# Current_Transducer.net
KiCad netlist of a schematic drawn in Altium Designer
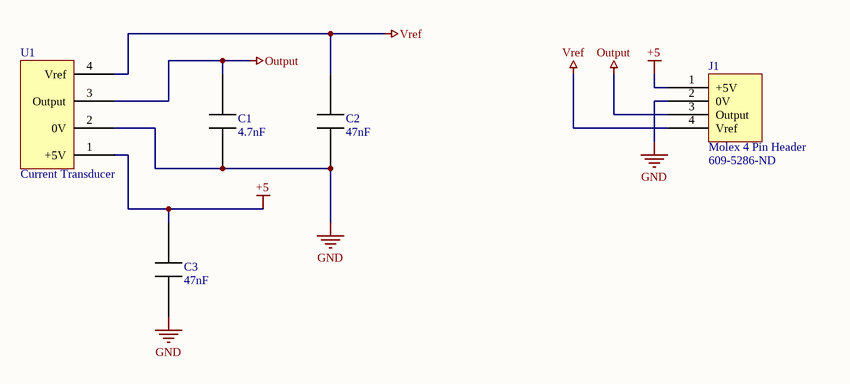
[diagram p0: Current Transducer.SchDoc]

(export (version "E")
  (design (tool "Eeschema 10.0.6"))
  (components
    (comp (ref "C1")
      (value "4.7nF")
      (footprint "CAPC2012X10N")
      (libsource (lib "Current Transducer") (part "47nF capacitor"))
    )
    (comp (ref "C2")
      (value "47nF")
      (footprint "CAPC2012X10N")
      (libsource (lib "Current Transducer") (part "47nF capacitor"))
    )
    (comp (ref "C3")
      (value "47nF")
      (footprint "CAPC2012X10N")
      (libsource (lib "Current Transducer") (part "47nF capacitor"))
    )
    (comp (ref "J1")
      (value "Molex 4 Pin Header")
      (footprint "4 Pin Header")
      (fields (field (name "SUPPLIER PART NUMBER 1") "609-5286-ND"))
      (libsource (lib "Current Transducer") (part "Molex 4 Pin Header"))
    )
    (comp (ref "U1")
      (value "Current Transducer")
      (footprint "Current Transducer")
      (libsource (lib "Current Transducer") (part "Current Transducer"))
    )
  )
  (nets
    (net (code "1") (name "+5") (class "Default")
      (node (ref "C3") (pin "2") (pinfunction "2_2") (pintype "passive"))
      (node (ref "J1") (pin "1") (pinfunction "+5V_1") (pintype "passive"))
      (node (ref "U1") (pin "1") (pinfunction "+5V_1") (pintype "passive"))
    )
    (net (code "2") (name "GND") (class "Default")
      (node (ref "C1") (pin "1") (pinfunction "1_1") (pintype "passive"))
      (node (ref "C2") (pin "1") (pinfunction "1_1") (pintype "passive"))
      (node (ref "C3") (pin "1") (pinfunction "1_1") (pintype "passive"))
      (node (ref "J1") (pin "2") (pinfunction "0V_2") (pintype "passive"))
      (node (ref "U1") (pin "2") (pinfunction "0V_2") (pintype "passive"))
    )
    (net (code "3") (name "Output") (class "Default")
      (node (ref "C1") (pin "2") (pinfunction "2_2") (pintype "passive"))
      (node (ref "J1") (pin "3") (pinfunction "Output_3") (pintype "passive"))
      (node (ref "U1") (pin "3") (pinfunction "Output_3") (pintype "passive"))
    )
    (net (code "4") (name "Vref") (class "Default")
      (node (ref "C2") (pin "2") (pinfunction "2_2") (pintype "passive"))
      (node (ref "J1") (pin "4") (pinfunction "Vref_4") (pintype "passive"))
      (node (ref "U1") (pin "4") (pinfunction "Vref_4") (pintype "passive"))
    )
  )
)
